# myRadioAddon.net
KiCad netlist of a schematic drawn in EAGLE
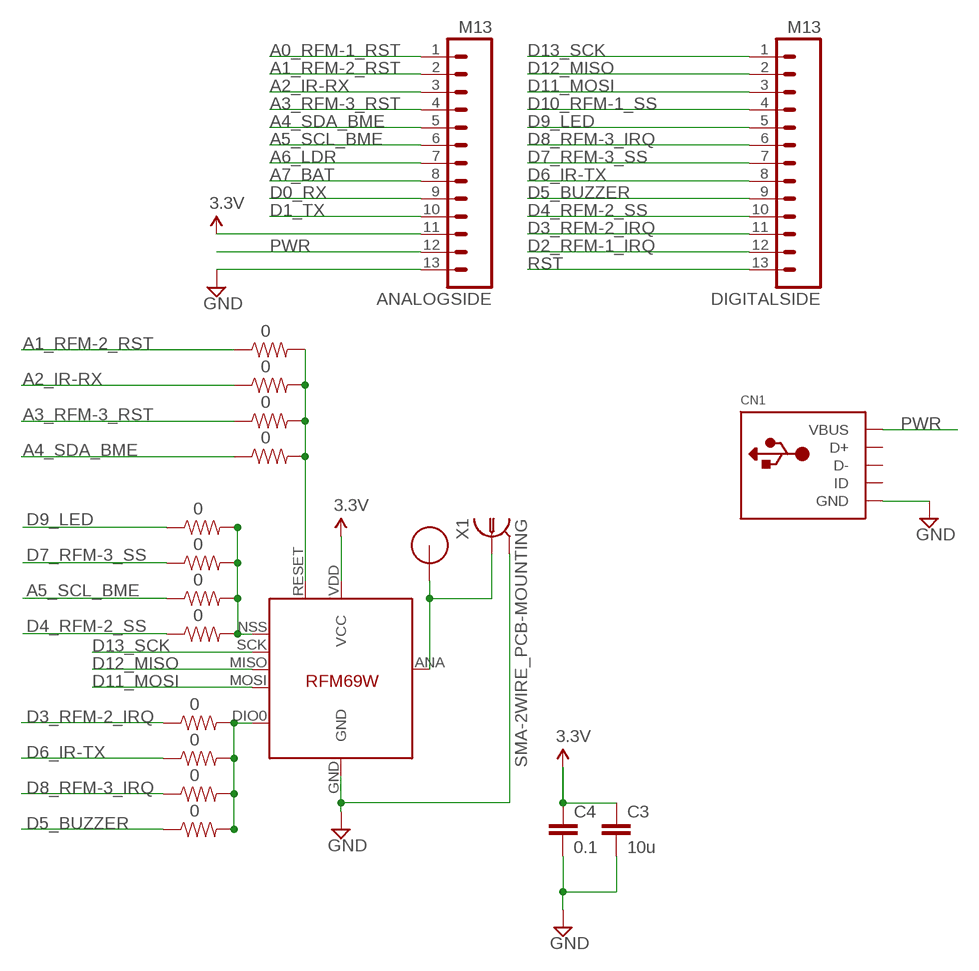
[diagram p0: schematic, sheet 1]

(export (version "E")
  (design (tool "Eeschema 10.0.6"))
  (components
    (comp (ref "ANALOGSIDE")
      (value "M13")
      (footprint "eagle-import:1X13")
      (libsource (lib "eagle-import") (part "M13"))
    )
    (comp (ref "C3")
      (value "10u")
      (footprint "eagle-import:0805-CAP")
      (libsource (lib "eagle-import") (part "CAP0805-CAP"))
    )
    (comp (ref "C4")
      (value "0.1")
      (footprint "eagle-import:0603-CAP")
      (libsource (lib "eagle-import") (part "CAP0603-CAP"))
    )
    (comp (ref "CN1")
      (value "USBMINIB")
      (footprint "eagle-import:USB-MINIB")
      (libsource (lib "eagle-import") (part "USBMINIB"))
    )
    (comp (ref "DIGITALSIDE")
      (value "M13")
      (footprint "eagle-import:1X13")
      (libsource (lib "eagle-import") (part "M13"))
    )
    (comp (ref "R1")
      (value "0")
      (footprint "eagle-import:0603-RES")
      (libsource (lib "eagle-import") (part "RESISTOR0603-RES"))
    )
    (comp (ref "R2")
      (value "0")
      (footprint "eagle-import:0603-RES")
      (libsource (lib "eagle-import") (part "RESISTOR0603-RES"))
    )
    (comp (ref "R3")
      (value "0")
      (footprint "eagle-import:0603-RES")
      (libsource (lib "eagle-import") (part "RESISTOR0603-RES"))
    )
    (comp (ref "R4")
      (value "0")
      (footprint "eagle-import:0603-RES")
      (libsource (lib "eagle-import") (part "RESISTOR0603-RES"))
    )
    (comp (ref "R5")
      (value "0")
      (footprint "eagle-import:0603-RES")
      (libsource (lib "eagle-import") (part "RESISTOR0603-RES"))
    )
    (comp (ref "R6")
      (value "0")
      (footprint "eagle-import:0603-RES")
      (libsource (lib "eagle-import") (part "RESISTOR0603-RES"))
    )
    (comp (ref "R7")
      (value "0")
      (footprint "eagle-import:0603-RES")
      (libsource (lib "eagle-import") (part "RESISTOR0603-RES"))
    )
    (comp (ref "R8")
      (value "0")
      (footprint "eagle-import:0603-RES")
      (libsource (lib "eagle-import") (part "RESISTOR0603-RES"))
    )
    (comp (ref "R9")
      (value "0")
      (footprint "eagle-import:0603-RES")
      (libsource (lib "eagle-import") (part "RESISTOR0603-RES"))
    )
    (comp (ref "R10")
      (value "0")
      (footprint "eagle-import:0603-RES")
      (libsource (lib "eagle-import") (part "RESISTOR0603-RES"))
    )
    (comp (ref "R11")
      (value "0")
      (footprint "eagle-import:0603-RES")
      (libsource (lib "eagle-import") (part "RESISTOR0603-RES"))
    )
    (comp (ref "R12")
      (value "0")
      (footprint "eagle-import:0603-RES")
      (libsource (lib "eagle-import") (part "RESISTOR0603-RES"))
    )
    (comp (ref "U$1")
      (value "RFM12B_ANTENNA")
      (footprint "eagle-import:RFM12B-ANTENNA")
      (libsource (lib "eagle-import") (part "RFM12B_ANTENNA"))
    )
    (comp (ref "U$5")
      (value "RFM69_MINIPADS")
      (footprint "eagle-import:RFM69W-MINPADS")
      (libsource (lib "eagle-import") (part "RFM69_MINIPADS"))
    )
    (comp (ref "X1")
      (value "SMA-2WIRE_PCB-MOUNTING")
      (footprint "eagle-import:J01151A0931")
      (libsource (lib "eagle-import") (part "SMA-2WIRE_PCB-MOUNTING"))
    )
  )
  (nets
    (net (code "1") (name "/A0_RFM-1_RST") (class "Default")
      (node (ref "ANALOGSIDE") (pin "1") (pinfunction "1_1") (pintype "passive"))
    )
    (net (code "2") (name "/A1_RFM-2_RST") (class "Default")
      (node (ref "ANALOGSIDE") (pin "2") (pinfunction "2_2") (pintype "passive"))
      (node (ref "R3") (pin "1") (pinfunction "1_1") (pintype "passive"))
    )
    (net (code "3") (name "/A2_IR-RX") (class "Default")
      (node (ref "ANALOGSIDE") (pin "3") (pinfunction "3_3") (pintype "passive"))
      (node (ref "R7") (pin "1") (pinfunction "1_1") (pintype "passive"))
    )
    (net (code "4") (name "/A3_RFM-3_RST") (class "Default")
      (node (ref "ANALOGSIDE") (pin "4") (pinfunction "4_4") (pintype "passive"))
      (node (ref "R4") (pin "1") (pinfunction "1_1") (pintype "passive"))
    )
    (net (code "5") (name "/A4_SDA_BME") (class "Default")
      (node (ref "ANALOGSIDE") (pin "5") (pinfunction "5_5") (pintype "passive"))
      (node (ref "R10") (pin "1") (pinfunction "1_1") (pintype "passive"))
    )
    (net (code "6") (name "/A5_SCL_BME") (class "Default")
      (node (ref "ANALOGSIDE") (pin "6") (pinfunction "6_6") (pintype "passive"))
      (node (ref "R11") (pin "1") (pinfunction "1_1") (pintype "passive"))
    )
    (net (code "7") (name "/A6_LDR") (class "Default")
      (node (ref "ANALOGSIDE") (pin "7") (pinfunction "7_7") (pintype "passive"))
    )
    (net (code "8") (name "/A7_BAT") (class "Default")
      (node (ref "ANALOGSIDE") (pin "8") (pinfunction "8_8") (pintype "passive"))
    )
    (net (code "9") (name "/D0_RX") (class "Default")
      (node (ref "ANALOGSIDE") (pin "9") (pinfunction "9_9") (pintype "passive"))
    )
    (net (code "10") (name "/D1_TX") (class "Default")
      (node (ref "ANALOGSIDE") (pin "10") (pinfunction "10_10") (pintype "passive"))
    )
    (net (code "11") (name "/D2_RFM-1_IRQ") (class "Default")
      (node (ref "DIGITALSIDE") (pin "12") (pinfunction "12_12") (pintype "passive"))
    )
    (net (code "12") (name "/D3_RFM-2_IRQ") (class "Default")
      (node (ref "DIGITALSIDE") (pin "11") (pinfunction "11_11") (pintype "passive"))
      (node (ref "R1") (pin "1") (pinfunction "1_1") (pintype "passive"))
    )
    (net (code "13") (name "/D4_RFM-2_SS") (class "Default")
      (node (ref "DIGITALSIDE") (pin "10") (pinfunction "10_10") (pintype "passive"))
      (node (ref "R2") (pin "1") (pinfunction "1_1") (pintype "passive"))
    )
    (net (code "14") (name "/D5_BUZZER") (class "Default")
      (node (ref "DIGITALSIDE") (pin "9") (pinfunction "9_9") (pintype "passive"))
      (node (ref "R9") (pin "1") (pinfunction "1_1") (pintype "passive"))
    )
    (net (code "15") (name "/D6_IR-TX") (class "Default")
      (node (ref "DIGITALSIDE") (pin "8") (pinfunction "8_8") (pintype "passive"))
      (node (ref "R12") (pin "1") (pinfunction "1_1") (pintype "passive"))
    )
    (net (code "16") (name "/D7_RFM-3_SS") (class "Default")
      (node (ref "DIGITALSIDE") (pin "7") (pinfunction "7_7") (pintype "passive"))
      (node (ref "R6") (pin "1") (pinfunction "1_1") (pintype "passive"))
    )
    (net (code "17") (name "/D8_RFM-3_IRQ") (class "Default")
      (node (ref "DIGITALSIDE") (pin "6") (pinfunction "6_6") (pintype "passive"))
      (node (ref "R5") (pin "1") (pinfunction "1_1") (pintype "passive"))
    )
    (net (code "18") (name "/D9_LED") (class "Default")
      (node (ref "DIGITALSIDE") (pin "5") (pinfunction "5_5") (pintype "passive"))
      (node (ref "R8") (pin "1") (pinfunction "1_1") (pintype "passive"))
    )
    (net (code "19") (name "/D10_RFM-1_SS") (class "Default")
      (node (ref "DIGITALSIDE") (pin "4") (pinfunction "4_4") (pintype "passive"))
    )
    (net (code "20") (name "/D11_MOSI") (class "Default")
      (node (ref "DIGITALSIDE") (pin "3") (pinfunction "3_3") (pintype "passive"))
      (node (ref "U$5") (pin "MOSI") (pinfunction "MOSI_MOSI") (pintype "output"))
    )
    (net (code "21") (name "/D12_MISO") (class "Default")
      (node (ref "DIGITALSIDE") (pin "2") (pinfunction "2_2") (pintype "passive"))
      (node (ref "U$5") (pin "MISO") (pinfunction "MISO_MISO") (pintype "input"))
    )
    (net (code "22") (name "/D13_SCK") (class "Default")
      (node (ref "DIGITALSIDE") (pin "1") (pinfunction "1_1") (pintype "passive"))
      (node (ref "U$5") (pin "SCK") (pinfunction "SCK_SCK") (pintype "input"))
    )
    (net (code "23") (name "/PWR") (class "Default")
      (node (ref "ANALOGSIDE") (pin "12") (pinfunction "12_12") (pintype "passive"))
      (node (ref "CN1") (pin "VBUS") (pinfunction "VBUS_VBUS") (pintype "power_in"))
    )
    (net (code "24") (name "/RST") (class "Default")
      (node (ref "DIGITALSIDE") (pin "13") (pinfunction "13_13") (pintype "passive"))
    )
    (net (code "25") (name "3.3V") (class "Default")
      (node (ref "ANALOGSIDE") (pin "11") (pinfunction "11_11") (pintype "passive"))
      (node (ref "C3") (pin "1") (pinfunction "1_1") (pintype "passive"))
      (node (ref "C4") (pin "1") (pinfunction "1_1") (pintype "passive"))
      (node (ref "U$5") (pin "VDD") (pinfunction "VCC_VDD") (pintype "power_in"))
    )
    (net (code "26") (name "GND") (class "Default")
      (node (ref "ANALOGSIDE") (pin "13") (pinfunction "13_13") (pintype "passive"))
      (node (ref "C3") (pin "2") (pinfunction "2_2") (pintype "passive"))
      (node (ref "C4") (pin "2") (pinfunction "2_2") (pintype "passive"))
      (node (ref "CN1") (pin "GND") (pinfunction "GND_GND") (pintype "power_in"))
      (node (ref "U$5") (pin "GND") (pinfunction "GND_GND") (pintype "power_in"))
      (node (ref "X1") (pin "G@1") (pinfunction "2_G@1") (pintype "passive"))
      (node (ref "X1") (pin "G@2") (pinfunction "2_G@2") (pintype "passive"))
      (node (ref "X1") (pin "G@3") (pinfunction "2_G@3") (pintype "passive"))
      (node (ref "X1") (pin "G@4") (pinfunction "2_G@4") (pintype "passive"))
    )
    (net (code "27") (name "Net-(R10-Pad2)") (class "Default")
      (node (ref "R10") (pin "2") (pinfunction "2_2") (pintype "passive"))
      (node (ref "R3") (pin "2") (pinfunction "2_2") (pintype "passive"))
      (node (ref "R4") (pin "2") (pinfunction "2_2") (pintype "passive"))
      (node (ref "R7") (pin "2") (pinfunction "2_2") (pintype "passive"))
      (node (ref "U$5") (pin "RESET") (pinfunction "RESET_RESET") (pintype "input"))
    )
    (net (code "28") (name "Net-(U$1-1)") (class "Default")
      (node (ref "U$1") (pin "P$1") (pinfunction "1_P$1") (pintype "bidirectional"))
      (node (ref "U$5") (pin "ANA") (pinfunction "ANT_ANA") (pintype "passive"))
      (node (ref "X1") (pin "1") (pinfunction "1_1") (pintype "passive"))
    )
    (net (code "29") (name "Net-(U$5-DIO0{slash}IRQ)") (class "Default")
      (node (ref "R1") (pin "2") (pinfunction "2_2") (pintype "passive"))
      (node (ref "R12") (pin "2") (pinfunction "2_2") (pintype "passive"))
      (node (ref "R5") (pin "2") (pinfunction "2_2") (pintype "passive"))
      (node (ref "R9") (pin "2") (pinfunction "2_2") (pintype "passive"))
      (node (ref "U$5") (pin "DIO0") (pinfunction "DIO0/IRQ_DIO0") (pintype "open_collector"))
    )
    (net (code "30") (name "Net-(U$5-SEL)") (class "Default")
      (node (ref "R11") (pin "2") (pinfunction "2_2") (pintype "passive"))
      (node (ref "R2") (pin "2") (pinfunction "2_2") (pintype "passive"))
      (node (ref "R6") (pin "2") (pinfunction "2_2") (pintype "passive"))
      (node (ref "R8") (pin "2") (pinfunction "2_2") (pintype "passive"))
      (node (ref "U$5") (pin "NSS") (pinfunction "SEL_NSS") (pintype "input"))
    )
    (net (code "31") (name "unconnected-(CN1-PadD+)") (class "Default")
      (node (ref "CN1") (pin "D+") (pinfunction "D+_D+") (pintype "bidirectional"))
    )
    (net (code "32") (name "unconnected-(CN1-PadD-)") (class "Default")
      (node (ref "CN1") (pin "D-") (pinfunction "D-_D-") (pintype "bidirectional"))
    )
    (net (code "33") (name "unconnected-(CN1-PadID)") (class "Default")
      (node (ref "CN1") (pin "ID") (pinfunction "ID_ID") (pintype "bidirectional"))
    )
  )
)
